# Filamint_Schematic_V3_1.net
KiCad netlist of a schematic drawn in EAGLE
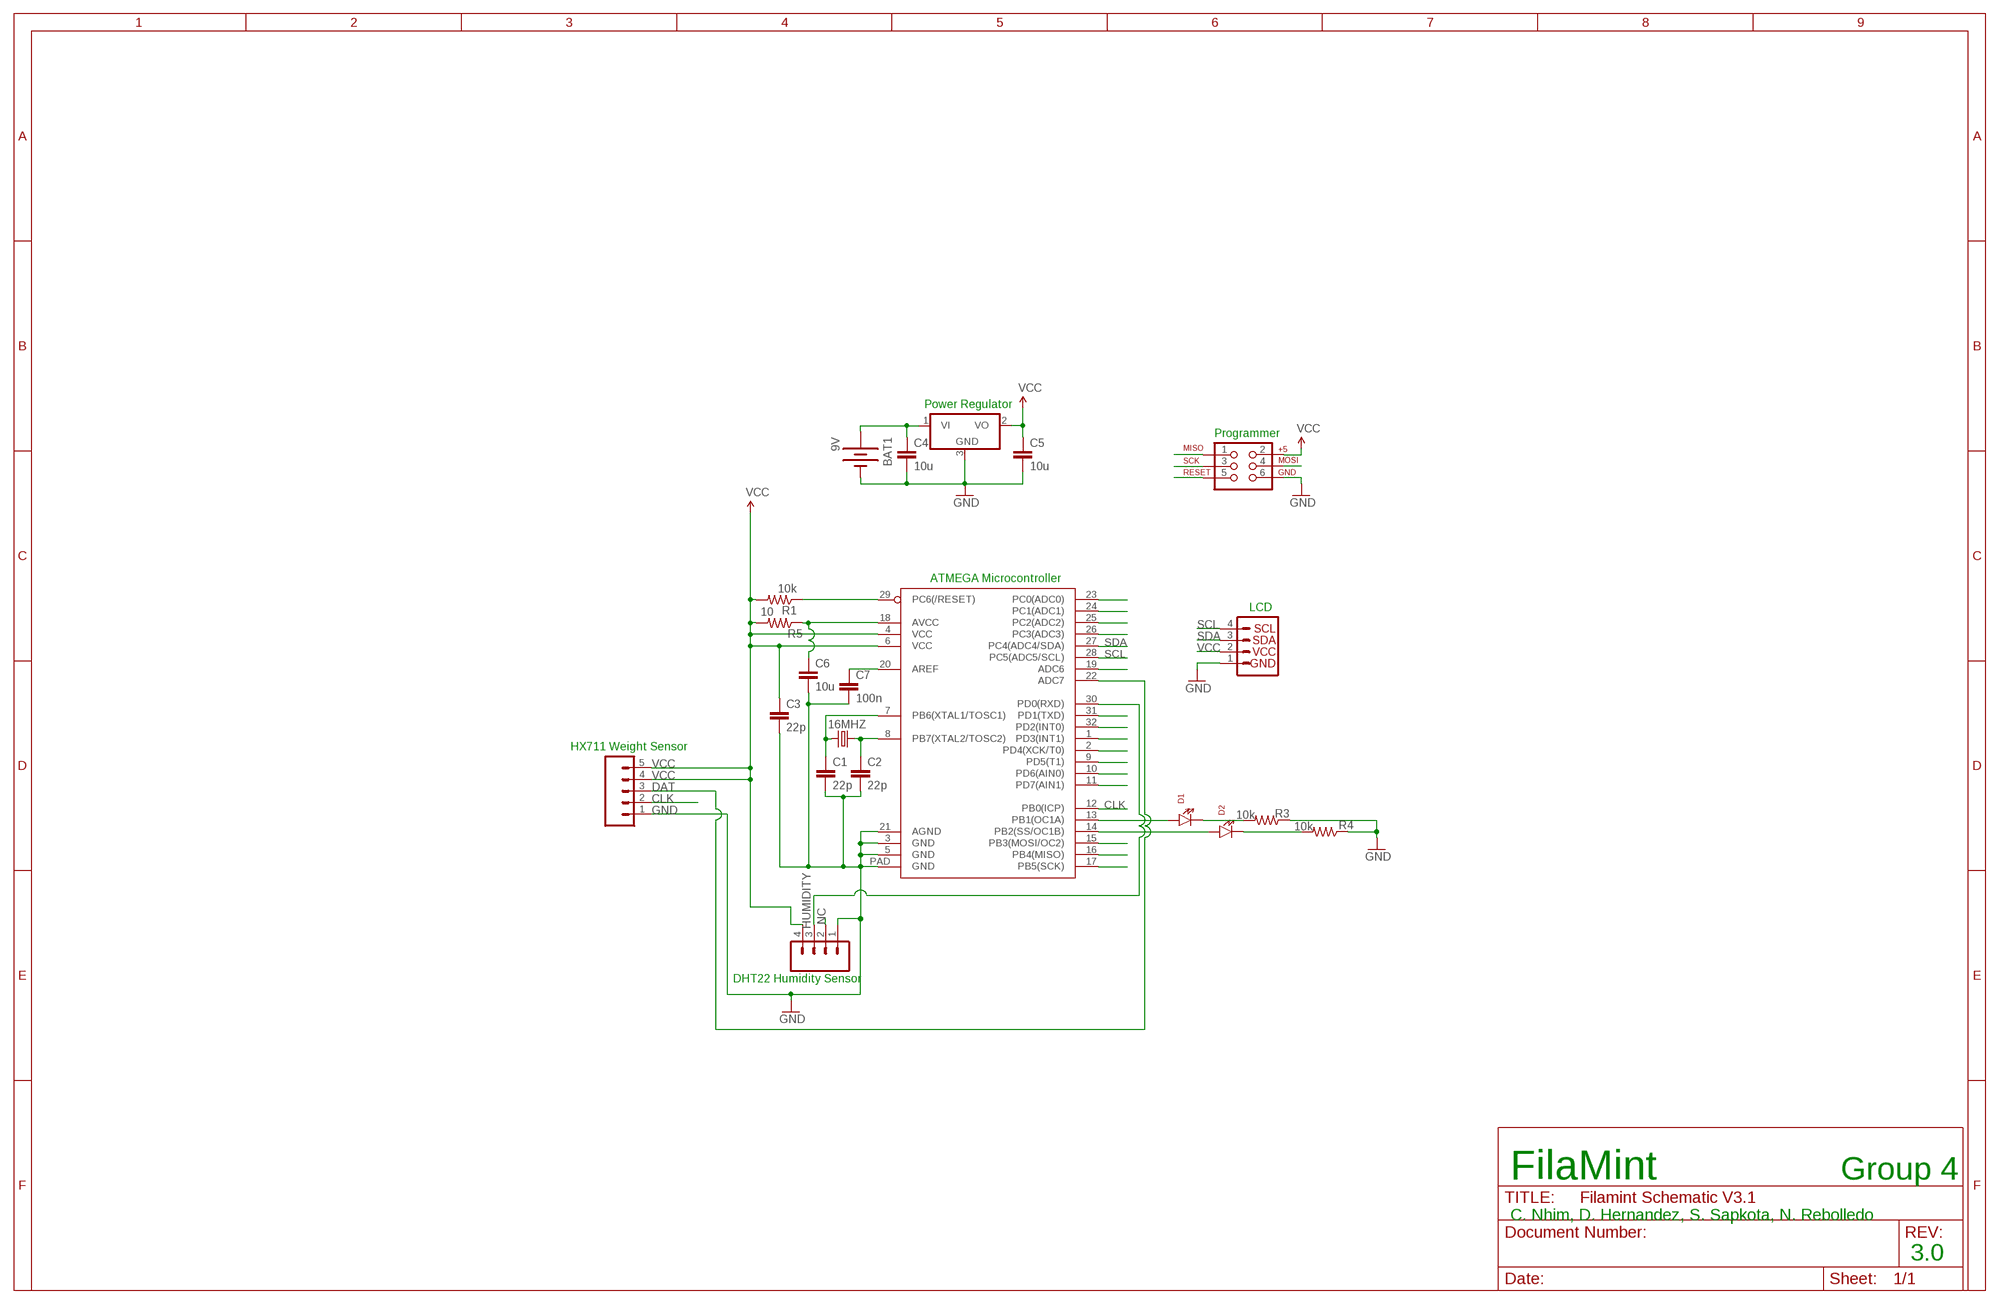
[diagram p0: schematic, sheet 1]

(export (version "E")
  (design (tool "Eeschema 10.0.6"))
  (components
    (comp (ref "16MHZ")
      (value "CSM-7X-DU")
      (footprint "eagle-import:CSM-7X-DU")
      (libsource (lib "eagle-import") (part "CSM-7X-DU"))
    )
    (comp (ref "BAT1")
      (value "9V")
      (footprint "eagle-import:BATTCON_9V")
      (libsource (lib "eagle-import") (part "BATTERY9V"))
    )
    (comp (ref "C1")
      (value "22p")
      (footprint "eagle-import:C025-024X044")
      (libsource (lib "eagle-import") (part "C-EU025-024X044"))
    )
    (comp (ref "C2")
      (value "22p")
      (footprint "eagle-import:C025-024X044")
      (libsource (lib "eagle-import") (part "C-EU025-024X044"))
    )
    (comp (ref "C3")
      (value "22p")
      (footprint "eagle-import:C025-024X044")
      (libsource (lib "eagle-import") (part "C-EU025-024X044"))
    )
    (comp (ref "C4")
      (value "10u")
      (footprint "eagle-import:C025-024X044")
      (libsource (lib "eagle-import") (part "C-EU025-024X044"))
    )
    (comp (ref "C5")
      (value "10u")
      (footprint "eagle-import:C025-024X044")
      (libsource (lib "eagle-import") (part "C-EU025-024X044"))
    )
    (comp (ref "C6")
      (value "10u")
      (footprint "eagle-import:C025-024X044")
      (libsource (lib "eagle-import") (part "C-EU025-024X044"))
    )
    (comp (ref "C7")
      (value "100n")
      (footprint "eagle-import:C025-024X044")
      (libsource (lib "eagle-import") (part "C-EU025-024X044"))
    )
    (comp (ref "D1")
      (value "LTE-302")
      (footprint "eagle-import:LTE-302")
      (libsource (lib "eagle-import") (part "LTE-302"))
    )
    (comp (ref "D2")
      (value "LTE-302")
      (footprint "eagle-import:LTE-302")
      (libsource (lib "eagle-import") (part "LTE-302"))
    )
    (comp (ref "DHT22")
      (value "M04SMD2")
      (footprint "eagle-import:1X04-1MM-RA")
      (libsource (lib "eagle-import") (part "M04SMD2"))
    )
    (comp (ref "HX711")
      (value "M05SMD")
      (footprint "eagle-import:1X05-1MM")
      (libsource (lib "eagle-import") (part "M05SMD"))
    )
    (comp (ref "IC1")
      (value "7805DT")
      (footprint "eagle-import:TO252")
      (libsource (lib "eagle-import") (part "78DT05"))
    )
    (comp (ref "LCD")
      (value "I2C_STANDARD")
      (footprint "eagle-import:1X04")
      (libsource (lib "eagle-import") (part "I2C_STANDARD"))
    )
    (comp (ref "MICROCONTROLLER")
      (value "ATMEGA328P_MLFMLF32")
      (footprint "eagle-import:MLF32-PAD")
      (libsource (lib "eagle-import") (part "ATMEGA328P_MLFMLF32"))
    )
    (comp (ref "PROGRAMMER")
      (value "AVR_SPI_PRG_6PTH")
      (footprint "eagle-import:2X3")
      (libsource (lib "eagle-import") (part "AVR_SPI_PRG_6PTH"))
    )
    (comp (ref "R1")
      (value "10k")
      (footprint "eagle-import:0204_5")
      (libsource (lib "eagle-import") (part "R-US_0204/5"))
    )
    (comp (ref "R3")
      (value "10k")
      (footprint "eagle-import:0204_5")
      (libsource (lib "eagle-import") (part "R-US_0204/5"))
    )
    (comp (ref "R4")
      (value "10k")
      (footprint "eagle-import:0204_5")
      (libsource (lib "eagle-import") (part "R-US_0204/5"))
    )
    (comp (ref "R5")
      (value "10")
      (footprint "eagle-import:0204_5")
      (libsource (lib "eagle-import") (part "R-US_0204/5"))
    )
  )
  (nets
    (net (code "1") (name "/CLK") (class "Default")
      (node (ref "HX711") (pin "2") (pinfunction "2_2") (pintype "passive"))
      (node (ref "MICROCONTROLLER") (pin "12") (pinfunction "PB0(ICP)_12") (pintype "bidirectional"))
    )
    (net (code "2") (name "/DAT") (class "Default")
      (node (ref "HX711") (pin "3") (pinfunction "3_3") (pintype "passive"))
      (node (ref "MICROCONTROLLER") (pin "22") (pinfunction "ADC7_22") (pintype "bidirectional"))
    )
    (net (code "3") (name "/HUMIDITY") (class "Default")
      (node (ref "DHT22") (pin "3") (pinfunction "3_3") (pintype "passive"))
      (node (ref "MICROCONTROLLER") (pin "30") (pinfunction "PD0(RXD)_30") (pintype "bidirectional"))
    )
    (net (code "4") (name "/MISO") (class "Default")
      (node (ref "MICROCONTROLLER") (pin "16") (pinfunction "PB4(MISO)_16") (pintype "bidirectional"))
      (node (ref "PROGRAMMER") (pin "1") (pinfunction "1_1") (pintype "passive"))
    )
    (net (code "5") (name "/MOSI") (class "Default")
      (node (ref "MICROCONTROLLER") (pin "15") (pinfunction "PB3(MOSI/OC2)_15") (pintype "bidirectional"))
      (node (ref "PROGRAMMER") (pin "4") (pinfunction "4_4") (pintype "passive"))
    )
    (net (code "6") (name "/NC") (class "Default")
      (node (ref "DHT22") (pin "2") (pinfunction "2_2") (pintype "passive"))
    )
    (net (code "7") (name "/SCK") (class "Default")
      (node (ref "MICROCONTROLLER") (pin "17") (pinfunction "PB5(SCK)_17") (pintype "bidirectional"))
      (node (ref "PROGRAMMER") (pin "3") (pinfunction "3_3") (pintype "passive"))
    )
    (net (code "8") (name "/SCL") (class "Default")
      (node (ref "LCD") (pin "4") (pinfunction "4_4") (pintype "passive"))
      (node (ref "MICROCONTROLLER") (pin "28") (pinfunction "PC5(ADC5/SCL)_28") (pintype "bidirectional"))
    )
    (net (code "9") (name "/SDA") (class "Default")
      (node (ref "LCD") (pin "3") (pinfunction "3_3") (pintype "passive"))
      (node (ref "MICROCONTROLLER") (pin "27") (pinfunction "PC4(ADC4/SDA)_27") (pintype "bidirectional"))
    )
    (net (code "10") (name "GND") (class "Default")
      (node (ref "BAT1") (pin "-") (pinfunction "-_-") (pintype "power_in"))
      (node (ref "C1") (pin "2") (pinfunction "2_2") (pintype "passive"))
      (node (ref "C2") (pin "2") (pinfunction "2_2") (pintype "passive"))
      (node (ref "C3") (pin "2") (pinfunction "2_2") (pintype "passive"))
      (node (ref "C4") (pin "2") (pinfunction "2_2") (pintype "passive"))
      (node (ref "C5") (pin "2") (pinfunction "2_2") (pintype "passive"))
      (node (ref "C6") (pin "2") (pinfunction "2_2") (pintype "passive"))
      (node (ref "C7") (pin "2") (pinfunction "2_2") (pintype "passive"))
      (node (ref "DHT22") (pin "1") (pinfunction "1_1") (pintype "passive"))
      (node (ref "HX711") (pin "1") (pinfunction "1_1") (pintype "passive"))
      (node (ref "IC1") (pin "3") (pinfunction "GND_3") (pintype "passive"))
      (node (ref "LCD") (pin "1") (pinfunction "1_1") (pintype "passive"))
      (node (ref "MICROCONTROLLER") (pin "21") (pinfunction "AGND_21") (pintype "bidirectional"))
      (node (ref "MICROCONTROLLER") (pin "3") (pinfunction "GND_3") (pintype "bidirectional"))
      (node (ref "MICROCONTROLLER") (pin "5") (pinfunction "GND_5") (pintype "bidirectional"))
      (node (ref "MICROCONTROLLER") (pin "PAD") (pinfunction "GND_PAD") (pintype "bidirectional"))
      (node (ref "PROGRAMMER") (pin "6") (pinfunction "6_6") (pintype "passive"))
      (node (ref "R3") (pin "1") (pinfunction "1_1") (pintype "passive"))
      (node (ref "R4") (pin "1") (pinfunction "1_1") (pintype "passive"))
    )
    (net (code "11") (name "Net-(D1-PadC)") (class "Default")
      (node (ref "D1") (pin "C") (pinfunction "C_C") (pintype "bidirectional"))
      (node (ref "R3") (pin "2") (pinfunction "2_2") (pintype "passive"))
    )
    (net (code "12") (name "Net-(D2-PadC)") (class "Default")
      (node (ref "D2") (pin "C") (pinfunction "C_C") (pintype "bidirectional"))
      (node (ref "R4") (pin "2") (pinfunction "2_2") (pintype "passive"))
    )
    (net (code "13") (name "Net-(IC1-VI)") (class "Default")
      (node (ref "BAT1") (pin "+") (pinfunction "+_+") (pintype "power_in"))
      (node (ref "C4") (pin "1") (pinfunction "1_1") (pintype "passive"))
      (node (ref "IC1") (pin "1") (pinfunction "VI_1") (pintype "input"))
    )
    (net (code "14") (name "Net-(MICROCONTROLLER-AREF)") (class "Default")
      (node (ref "C7") (pin "1") (pinfunction "1_1") (pintype "passive"))
      (node (ref "MICROCONTROLLER") (pin "20") (pinfunction "AREF_20") (pintype "bidirectional"))
    )
    (net (code "15") (name "Net-(MICROCONTROLLER-AVCC)") (class "Default")
      (node (ref "C6") (pin "1") (pinfunction "1_1") (pintype "passive"))
      (node (ref "MICROCONTROLLER") (pin "18") (pinfunction "AVCC_18") (pintype "bidirectional"))
      (node (ref "R5") (pin "1") (pinfunction "1_1") (pintype "passive"))
    )
    (net (code "16") (name "Net-(MICROCONTROLLER-PB1(OC1A))") (class "Default")
      (node (ref "D1") (pin "A") (pinfunction "A_A") (pintype "bidirectional"))
      (node (ref "MICROCONTROLLER") (pin "13") (pinfunction "PB1(OC1A)_13") (pintype "bidirectional"))
    )
    (net (code "17") (name "Net-(MICROCONTROLLER-PB2(SS{slash}OC1B))") (class "Default")
      (node (ref "D2") (pin "A") (pinfunction "A_A") (pintype "bidirectional"))
      (node (ref "MICROCONTROLLER") (pin "14") (pinfunction "PB2(SS/OC1B)_14") (pintype "bidirectional"))
    )
    (net (code "18") (name "Net-(MICROCONTROLLER-PB6(XTAL1{slash}TOSC1))") (class "Default")
      (node (ref "16MHZ") (pin "2") (pinfunction "2_2") (pintype "passive"))
      (node (ref "C1") (pin "1") (pinfunction "1_1") (pintype "passive"))
      (node (ref "MICROCONTROLLER") (pin "7") (pinfunction "PB6(XTAL1/TOSC1)_7") (pintype "bidirectional"))
    )
    (net (code "19") (name "Net-(MICROCONTROLLER-PB7(XTAL2{slash}TOSC2))") (class "Default")
      (node (ref "16MHZ") (pin "1") (pinfunction "1_1") (pintype "passive"))
      (node (ref "C2") (pin "1") (pinfunction "1_1") (pintype "passive"))
      (node (ref "MICROCONTROLLER") (pin "8") (pinfunction "PB7(XTAL2/TOSC2)_8") (pintype "bidirectional"))
    )
    (net (code "20") (name "Net-(MICROCONTROLLER-PC6({slash}RESET))") (class "Default")
      (node (ref "MICROCONTROLLER") (pin "29") (pinfunction "PC6(/RESET)_29") (pintype "bidirectional"))
      (node (ref "R1") (pin "1") (pinfunction "1_1") (pintype "passive"))
    )
    (net (code "21") (name "VCC") (class "Default")
      (node (ref "C3") (pin "1") (pinfunction "1_1") (pintype "passive"))
      (node (ref "C5") (pin "1") (pinfunction "1_1") (pintype "passive"))
      (node (ref "DHT22") (pin "4") (pinfunction "4_4") (pintype "passive"))
      (node (ref "HX711") (pin "4") (pinfunction "4_4") (pintype "passive"))
      (node (ref "HX711") (pin "5") (pinfunction "5_5") (pintype "passive"))
      (node (ref "IC1") (pin "2") (pinfunction "VO_2") (pintype "passive"))
      (node (ref "LCD") (pin "2") (pinfunction "2_2") (pintype "passive"))
      (node (ref "MICROCONTROLLER") (pin "4") (pinfunction "VCC_4") (pintype "bidirectional"))
      (node (ref "MICROCONTROLLER") (pin "6") (pinfunction "VCC_6") (pintype "bidirectional"))
      (node (ref "PROGRAMMER") (pin "2") (pinfunction "2_2") (pintype "passive"))
      (node (ref "R1") (pin "2") (pinfunction "2_2") (pintype "passive"))
      (node (ref "R5") (pin "2") (pinfunction "2_2") (pintype "passive"))
    )
    (net (code "22") (name "unconnected-(MICROCONTROLLER-ADC6-Pad19)") (class "Default")
      (node (ref "MICROCONTROLLER") (pin "19") (pinfunction "ADC6_19") (pintype "bidirectional"))
    )
    (net (code "23") (name "unconnected-(MICROCONTROLLER-PC0(ADC0)-Pad23)") (class "Default")
      (node (ref "MICROCONTROLLER") (pin "23") (pinfunction "PC0(ADC0)_23") (pintype "bidirectional"))
    )
    (net (code "24") (name "unconnected-(MICROCONTROLLER-PC1(ADC1)-Pad24)") (class "Default")
      (node (ref "MICROCONTROLLER") (pin "24") (pinfunction "PC1(ADC1)_24") (pintype "bidirectional"))
    )
    (net (code "25") (name "unconnected-(MICROCONTROLLER-PC2(ADC2)-Pad25)") (class "Default")
      (node (ref "MICROCONTROLLER") (pin "25") (pinfunction "PC2(ADC2)_25") (pintype "bidirectional"))
    )
    (net (code "26") (name "unconnected-(MICROCONTROLLER-PC3(ADC3)-Pad26)") (class "Default")
      (node (ref "MICROCONTROLLER") (pin "26") (pinfunction "PC3(ADC3)_26") (pintype "bidirectional"))
    )
    (net (code "27") (name "unconnected-(MICROCONTROLLER-PD1(TXD)-Pad31)") (class "Default")
      (node (ref "MICROCONTROLLER") (pin "31") (pinfunction "PD1(TXD)_31") (pintype "bidirectional"))
    )
    (net (code "28") (name "unconnected-(MICROCONTROLLER-PD2(INT0)-Pad32)") (class "Default")
      (node (ref "MICROCONTROLLER") (pin "32") (pinfunction "PD2(INT0)_32") (pintype "bidirectional"))
    )
    (net (code "29") (name "unconnected-(MICROCONTROLLER-PD3(INT1)-Pad1)") (class "Default")
      (node (ref "MICROCONTROLLER") (pin "1") (pinfunction "PD3(INT1)_1") (pintype "bidirectional"))
    )
    (net (code "30") (name "unconnected-(MICROCONTROLLER-PD4(XCK{slash}T0)-Pad2)") (class "Default")
      (node (ref "MICROCONTROLLER") (pin "2") (pinfunction "PD4(XCK/T0)_2") (pintype "bidirectional"))
    )
    (net (code "31") (name "unconnected-(MICROCONTROLLER-PD5(T1)-Pad9)") (class "Default")
      (node (ref "MICROCONTROLLER") (pin "9") (pinfunction "PD5(T1)_9") (pintype "bidirectional"))
    )
    (net (code "32") (name "unconnected-(MICROCONTROLLER-PD6(AIN0)-Pad10)") (class "Default")
      (node (ref "MICROCONTROLLER") (pin "10") (pinfunction "PD6(AIN0)_10") (pintype "bidirectional"))
    )
    (net (code "33") (name "unconnected-(MICROCONTROLLER-PD7(AIN1)-Pad11)") (class "Default")
      (node (ref "MICROCONTROLLER") (pin "11") (pinfunction "PD7(AIN1)_11") (pintype "bidirectional"))
    )
    (net (code "34") (name "unconnected-(PROGRAMMER-Pad5)") (class "Default")
      (node (ref "PROGRAMMER") (pin "5") (pinfunction "5_5") (pintype "passive"))
    )
  )
)
